# ESPswitch.net
KiCad netlist of a schematic drawn in EAGLE
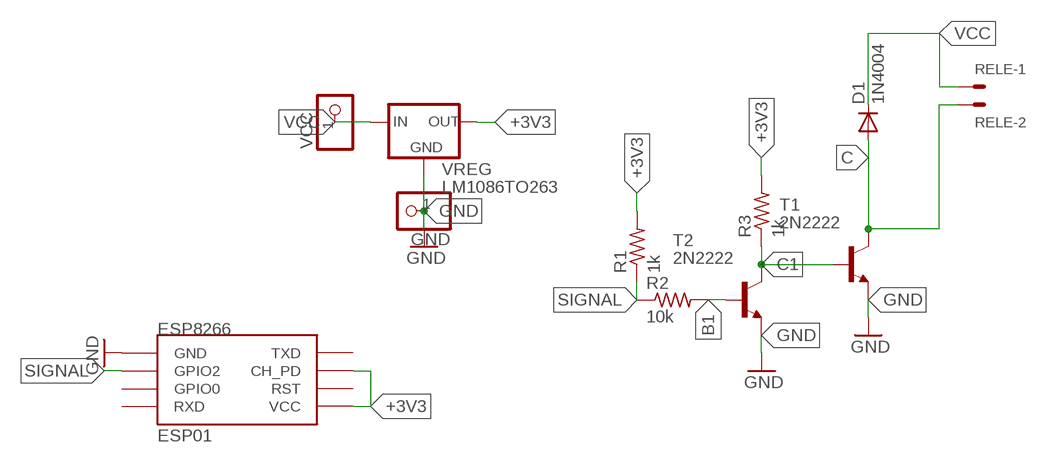
[diagram p0: schematic, sheet 1]

(export (version "E")
  (design (tool "Eeschema 10.0.6"))
  (components
    (comp (ref "D1")
      (value "1N4004")
      (footprint "eagle-import:DO41-10")
      (libsource (lib "eagle-import") (part "1N4004"))
    )
    (comp (ref "ESP8266")
      (value "ESP01")
      (footprint "eagle-import:ESP01")
      (libsource (lib "eagle-import") (part "ESP01"))
    )
    (comp (ref "GND")
      (value "PINHD-1X1")
      (footprint "eagle-import:1X01")
      (libsource (lib "eagle-import") (part "PINHD-1X1"))
    )
    (comp (ref "R1")
      (value "1k")
      (footprint "eagle-import:0309_12")
      (libsource (lib "eagle-import") (part "R-US_0309/12"))
    )
    (comp (ref "R2")
      (value "10k")
      (footprint "eagle-import:0309_12")
      (libsource (lib "eagle-import") (part "R-US_0309/12"))
    )
    (comp (ref "R3")
      (value "1k")
      (footprint "eagle-import:0309_12")
      (libsource (lib "eagle-import") (part "R-US_0309/12"))
    )
    (comp (ref "RELE")
      (value "22-23-2021")
      (footprint "eagle-import:22-23-2021")
      (fields (field (name "MF") "MOLEX"))
      (libsource (lib "eagle-import") (part "22-23-2021"))
    )
    (comp (ref "T1")
      (value "2N2222")
      (footprint "eagle-import:TO92-EBC-OVAL")
      (libsource (lib "eagle-import") (part "2N2222"))
    )
    (comp (ref "T2")
      (value "2N2222")
      (footprint "eagle-import:TO92-EBC-OVAL")
      (libsource (lib "eagle-import") (part "2N2222"))
    )
    (comp (ref "VCC")
      (value "PINHD-1X1")
      (footprint "eagle-import:1X01")
      (libsource (lib "eagle-import") (part "PINHD-1X1"))
    )
    (comp (ref "VREG")
      (value "LM1086TO263")
      (footprint "eagle-import:TO263")
      (libsource (lib "eagle-import") (part "LM1086TO263"))
    )
  )
  (nets
    (net (code "1") (name "+3V3") (class "Default")
      (node (ref "ESP8266") (pin "CH_PD") (pinfunction "CH_PD_CH_PD") (pintype "bidirectional"))
      (node (ref "ESP8266") (pin "VCC") (pinfunction "VCC_VCC") (pintype "bidirectional"))
      (node (ref "R1") (pin "2") (pinfunction "2_2") (pintype "passive"))
      (node (ref "R3") (pin "2") (pinfunction "2_2") (pintype "passive"))
      (node (ref "VREG") (pin "2") (pinfunction "OUT_2") (pintype "passive"))
    )
    (net (code "2") (name "B1") (class "Default")
      (node (ref "R2") (pin "2") (pinfunction "2_2") (pintype "passive"))
      (node (ref "T2") (pin "B") (pinfunction "B_B") (pintype "passive"))
    )
    (net (code "3") (name "C") (class "Default")
      (node (ref "D1") (pin "A") (pinfunction "A_A") (pintype "passive"))
      (node (ref "RELE") (pin "2") (pinfunction "S_2") (pintype "passive"))
      (node (ref "T1") (pin "C") (pinfunction "C_C") (pintype "passive"))
    )
    (net (code "4") (name "C1") (class "Default")
      (node (ref "R3") (pin "1") (pinfunction "1_1") (pintype "passive"))
      (node (ref "T1") (pin "B") (pinfunction "B_B") (pintype "passive"))
      (node (ref "T2") (pin "C") (pinfunction "C_C") (pintype "passive"))
    )
    (net (code "5") (name "GND") (class "Default")
      (node (ref "ESP8266") (pin "GND") (pinfunction "GND_GND") (pintype "bidirectional"))
      (node (ref "GND") (pin "1") (pinfunction "1_1") (pintype "passive"))
      (node (ref "T1") (pin "E") (pinfunction "E_E") (pintype "passive"))
      (node (ref "T2") (pin "E") (pinfunction "E_E") (pintype "passive"))
      (node (ref "VREG") (pin "1") (pinfunction "GND_1") (pintype "input"))
    )
    (net (code "6") (name "SIGNAL") (class "Default")
      (node (ref "ESP8266") (pin "GPIO2") (pinfunction "GPIO2_GPIO2") (pintype "bidirectional"))
      (node (ref "R1") (pin "1") (pinfunction "1_1") (pintype "passive"))
      (node (ref "R2") (pin "1") (pinfunction "1_1") (pintype "passive"))
    )
    (net (code "7") (name "VCC") (class "Default")
      (node (ref "D1") (pin "C") (pinfunction "C_C") (pintype "passive"))
      (node (ref "RELE") (pin "1") (pinfunction "S_1") (pintype "passive"))
      (node (ref "VCC") (pin "1") (pinfunction "1_1") (pintype "passive"))
      (node (ref "VREG") (pin "3") (pinfunction "IN_3") (pintype "input"))
    )
    (net (code "8") (name "unconnected-(ESP8266-PadGPIO0)") (class "Default")
      (node (ref "ESP8266") (pin "GPIO0") (pinfunction "GPIO0_GPIO0") (pintype "bidirectional"))
    )
    (net (code "9") (name "unconnected-(ESP8266-PadRST)") (class "Default")
      (node (ref "ESP8266") (pin "RST") (pinfunction "RST_RST") (pintype "bidirectional"))
    )
    (net (code "10") (name "unconnected-(ESP8266-RXD-PadRX)") (class "Default")
      (node (ref "ESP8266") (pin "RX") (pinfunction "RXD_RX") (pintype "bidirectional"))
    )
    (net (code "11") (name "unconnected-(ESP8266-TXD-PadTX)") (class "Default")
      (node (ref "ESP8266") (pin "TX") (pinfunction "TXD_TX") (pintype "bidirectional"))
    )
  )
)
